# SensorLaser.net
KiCad netlist of a schematic drawn in EAGLE
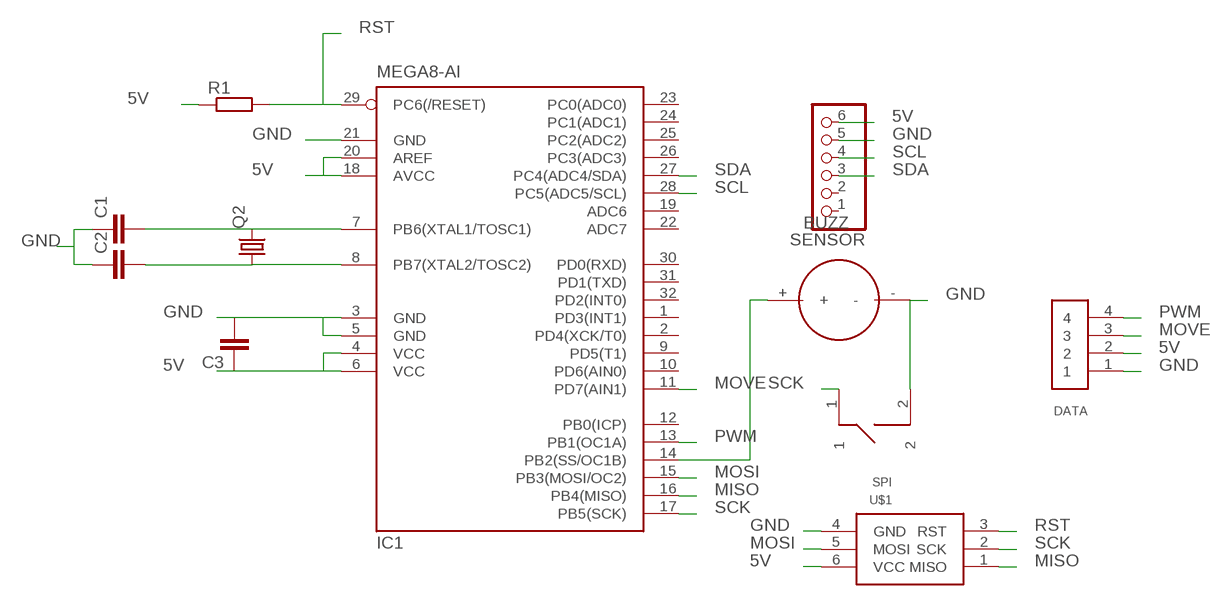
[diagram p0: schematic, sheet 1]

(export (version "E")
  (design (tool "Eeschema 10.0.6"))
  (components
    (comp (ref "BUZZ")
      (value "KSQ-601BP")
      (footprint "eagle-import:KSQ-601BP")
      (libsource (lib "eagle-import") (part "KSQ-601BP"))
    )
    (comp (ref "C1")
      (value "C-EUC0402K")
      (footprint "eagle-import:C0402K")
      (libsource (lib "eagle-import") (part "C-EUC0402K"))
    )
    (comp (ref "C2")
      (value "C-EUC0402K")
      (footprint "eagle-import:C0402K")
      (libsource (lib "eagle-import") (part "C-EUC0402K"))
    )
    (comp (ref "C3")
      (value "C-EUC0402K")
      (footprint "eagle-import:C0402K")
      (libsource (lib "eagle-import") (part "C-EUC0402K"))
    )
    (comp (ref "DATA")
      (value "CP150_1X4")
      (footprint "eagle-import:CP150_1X4")
      (libsource (lib "eagle-import") (part "CP150_1X4"))
    )
    (comp (ref "IC1")
      (value "MEGA8-AI")
      (footprint "eagle-import:TQFP32-08")
      (fields (field (name "MPN") "ATMEGA8-16AU"))
      (libsource (lib "eagle-import") (part "MEGA8-AI"))
    )
    (comp (ref "Q2")
      (value "CRYSTALHC49U70")
      (footprint "eagle-import:HC49U70")
      (libsource (lib "eagle-import") (part "CRYSTALHC49U70"))
    )
    (comp (ref "R1")
      (value "R-EU_M1206")
      (footprint "eagle-import:M1206")
      (libsource (lib "eagle-import") (part "R-EU_M1206"))
    )
    (comp (ref "SENSOR")
      (value "PINHD-1X6")
      (footprint "eagle-import:1X06")
      (libsource (lib "eagle-import") (part "PINHD-1X6"))
    )
    (comp (ref "U$1")
      (value "SPI")
      (footprint "eagle-import:HEAD-2X3")
      (libsource (lib "eagle-import") (part "SPI"))
    )
    (comp (ref "U$2")
      (value "PUSH_MEC")
      (footprint "eagle-import:PUSH_MECANICO")
      (libsource (lib "eagle-import") (part "PUSH_MEC"))
    )
  )
  (nets
    (net (code "1") (name "/5V") (class "Default")
      (node (ref "C3") (pin "1") (pinfunction "1_1") (pintype "passive"))
      (node (ref "DATA") (pin "2") (pinfunction "2_2") (pintype "bidirectional"))
      (node (ref "IC1") (pin "18") (pinfunction "AVCC_18") (pintype "power_in"))
      (node (ref "IC1") (pin "20") (pinfunction "AREF_20") (pintype "passive"))
      (node (ref "IC1") (pin "4") (pinfunction "VCC_4") (pintype "power_in"))
      (node (ref "IC1") (pin "6") (pinfunction "VCC_6") (pintype "power_in"))
      (node (ref "R1") (pin "1") (pinfunction "1_1") (pintype "passive"))
      (node (ref "SENSOR") (pin "6") (pinfunction "6_6") (pintype "passive"))
      (node (ref "U$1") (pin "6") (pinfunction "VCC_6") (pintype "bidirectional"))
    )
    (net (code "2") (name "/GND") (class "Default")
      (node (ref "BUZZ") (pin "-") (pinfunction "-_-") (pintype "bidirectional"))
      (node (ref "C1") (pin "1") (pinfunction "1_1") (pintype "passive"))
      (node (ref "C2") (pin "1") (pinfunction "1_1") (pintype "passive"))
      (node (ref "C3") (pin "2") (pinfunction "2_2") (pintype "passive"))
      (node (ref "DATA") (pin "1") (pinfunction "1_1") (pintype "bidirectional"))
      (node (ref "IC1") (pin "21") (pinfunction "GND_21") (pintype "power_in"))
      (node (ref "IC1") (pin "3") (pinfunction "GND_3") (pintype "power_in"))
      (node (ref "IC1") (pin "5") (pinfunction "GND_5") (pintype "power_in"))
      (node (ref "SENSOR") (pin "5") (pinfunction "5_5") (pintype "passive"))
      (node (ref "U$1") (pin "4") (pinfunction "GND_4") (pintype "bidirectional"))
      (node (ref "U$2") (pin "2") (pinfunction "2_2") (pintype "bidirectional"))
    )
    (net (code "3") (name "/MISO") (class "Default")
      (node (ref "IC1") (pin "16") (pinfunction "PB4(MISO)_16") (pintype "bidirectional"))
      (node (ref "U$1") (pin "1") (pinfunction "MISO_1") (pintype "bidirectional"))
    )
    (net (code "4") (name "/MOSI") (class "Default")
      (node (ref "IC1") (pin "15") (pinfunction "PB3(MOSI/OC2)_15") (pintype "bidirectional"))
      (node (ref "U$1") (pin "5") (pinfunction "MOSI_5") (pintype "bidirectional"))
    )
    (net (code "5") (name "/MOVE") (class "Default")
      (node (ref "DATA") (pin "3") (pinfunction "3_3") (pintype "bidirectional"))
      (node (ref "IC1") (pin "11") (pinfunction "PD7(AIN1)_11") (pintype "bidirectional"))
    )
    (net (code "6") (name "/PWM") (class "Default")
      (node (ref "DATA") (pin "4") (pinfunction "4_4") (pintype "bidirectional"))
      (node (ref "IC1") (pin "13") (pinfunction "PB1(OC1A)_13") (pintype "bidirectional"))
    )
    (net (code "7") (name "/RST") (class "Default")
      (node (ref "IC1") (pin "29") (pinfunction "PC6(/RESET)_29") (pintype "bidirectional"))
      (node (ref "R1") (pin "2") (pinfunction "2_2") (pintype "passive"))
      (node (ref "U$1") (pin "3") (pinfunction "RST_3") (pintype "bidirectional"))
    )
    (net (code "8") (name "/SCK") (class "Default")
      (node (ref "IC1") (pin "17") (pinfunction "PB5(SCK)_17") (pintype "bidirectional"))
      (node (ref "U$1") (pin "2") (pinfunction "SCK_2") (pintype "bidirectional"))
      (node (ref "U$2") (pin "1") (pinfunction "1_1") (pintype "bidirectional"))
    )
    (net (code "9") (name "/SCL") (class "Default")
      (node (ref "IC1") (pin "28") (pinfunction "PC5(ADC5/SCL)_28") (pintype "bidirectional"))
      (node (ref "SENSOR") (pin "4") (pinfunction "4_4") (pintype "passive"))
    )
    (net (code "10") (name "/SDA") (class "Default")
      (node (ref "IC1") (pin "27") (pinfunction "PC4(ADC4/SDA)_27") (pintype "bidirectional"))
      (node (ref "SENSOR") (pin "3") (pinfunction "3_3") (pintype "passive"))
    )
    (net (code "11") (name "Net-(IC1-PB2(SS{slash}OC1B))") (class "Default")
      (node (ref "BUZZ") (pin "+") (pinfunction "+_+") (pintype "bidirectional"))
      (node (ref "IC1") (pin "14") (pinfunction "PB2(SS/OC1B)_14") (pintype "bidirectional"))
    )
    (net (code "12") (name "Net-(IC1-PB6(XTAL1{slash}TOSC1))") (class "Default")
      (node (ref "C1") (pin "2") (pinfunction "2_2") (pintype "passive"))
      (node (ref "IC1") (pin "7") (pinfunction "PB6(XTAL1/TOSC1)_7") (pintype "bidirectional"))
      (node (ref "Q2") (pin "2") (pinfunction "2_2") (pintype "passive"))
    )
    (net (code "13") (name "Net-(IC1-PB7(XTAL2{slash}TOSC2))") (class "Default")
      (node (ref "C2") (pin "2") (pinfunction "2_2") (pintype "passive"))
      (node (ref "IC1") (pin "8") (pinfunction "PB7(XTAL2/TOSC2)_8") (pintype "bidirectional"))
      (node (ref "Q2") (pin "1") (pinfunction "1_1") (pintype "passive"))
    )
    (net (code "14") (name "unconnected-(IC1-ADC6-Pad19)") (class "Default")
      (node (ref "IC1") (pin "19") (pinfunction "ADC6_19") (pintype "bidirectional"))
    )
    (net (code "15") (name "unconnected-(IC1-ADC7-Pad22)") (class "Default")
      (node (ref "IC1") (pin "22") (pinfunction "ADC7_22") (pintype "bidirectional"))
    )
    (net (code "16") (name "unconnected-(IC1-PB0(ICP)-Pad12)") (class "Default")
      (node (ref "IC1") (pin "12") (pinfunction "PB0(ICP)_12") (pintype "bidirectional"))
    )
    (net (code "17") (name "unconnected-(IC1-PC0(ADC0)-Pad23)") (class "Default")
      (node (ref "IC1") (pin "23") (pinfunction "PC0(ADC0)_23") (pintype "bidirectional"))
    )
    (net (code "18") (name "unconnected-(IC1-PC1(ADC1)-Pad24)") (class "Default")
      (node (ref "IC1") (pin "24") (pinfunction "PC1(ADC1)_24") (pintype "bidirectional"))
    )
    (net (code "19") (name "unconnected-(IC1-PC2(ADC2)-Pad25)") (class "Default")
      (node (ref "IC1") (pin "25") (pinfunction "PC2(ADC2)_25") (pintype "bidirectional"))
    )
    (net (code "20") (name "unconnected-(IC1-PC3(ADC3)-Pad26)") (class "Default")
      (node (ref "IC1") (pin "26") (pinfunction "PC3(ADC3)_26") (pintype "bidirectional"))
    )
    (net (code "21") (name "unconnected-(IC1-PD0(RXD)-Pad30)") (class "Default")
      (node (ref "IC1") (pin "30") (pinfunction "PD0(RXD)_30") (pintype "bidirectional"))
    )
    (net (code "22") (name "unconnected-(IC1-PD1(TXD)-Pad31)") (class "Default")
      (node (ref "IC1") (pin "31") (pinfunction "PD1(TXD)_31") (pintype "bidirectional"))
    )
    (net (code "23") (name "unconnected-(IC1-PD2(INT0)-Pad32)") (class "Default")
      (node (ref "IC1") (pin "32") (pinfunction "PD2(INT0)_32") (pintype "bidirectional"))
    )
    (net (code "24") (name "unconnected-(IC1-PD3(INT1)-Pad1)") (class "Default")
      (node (ref "IC1") (pin "1") (pinfunction "PD3(INT1)_1") (pintype "bidirectional"))
    )
    (net (code "25") (name "unconnected-(IC1-PD4(XCK{slash}T0)-Pad2)") (class "Default")
      (node (ref "IC1") (pin "2") (pinfunction "PD4(XCK/T0)_2") (pintype "bidirectional"))
    )
    (net (code "26") (name "unconnected-(IC1-PD5(T1)-Pad9)") (class "Default")
      (node (ref "IC1") (pin "9") (pinfunction "PD5(T1)_9") (pintype "bidirectional"))
    )
    (net (code "27") (name "unconnected-(IC1-PD6(AIN0)-Pad10)") (class "Default")
      (node (ref "IC1") (pin "10") (pinfunction "PD6(AIN0)_10") (pintype "bidirectional"))
    )
    (net (code "28") (name "unconnected-(SENSOR-Pad1)") (class "Default")
      (node (ref "SENSOR") (pin "1") (pinfunction "1_1") (pintype "passive"))
    )
    (net (code "29") (name "unconnected-(SENSOR-Pad2)") (class "Default")
      (node (ref "SENSOR") (pin "2") (pinfunction "2_2") (pintype "passive"))
    )
  )
)
